# lab6_2020-12-28_17-35-51.net
KiCad netlist of a schematic drawn in EasyEDA
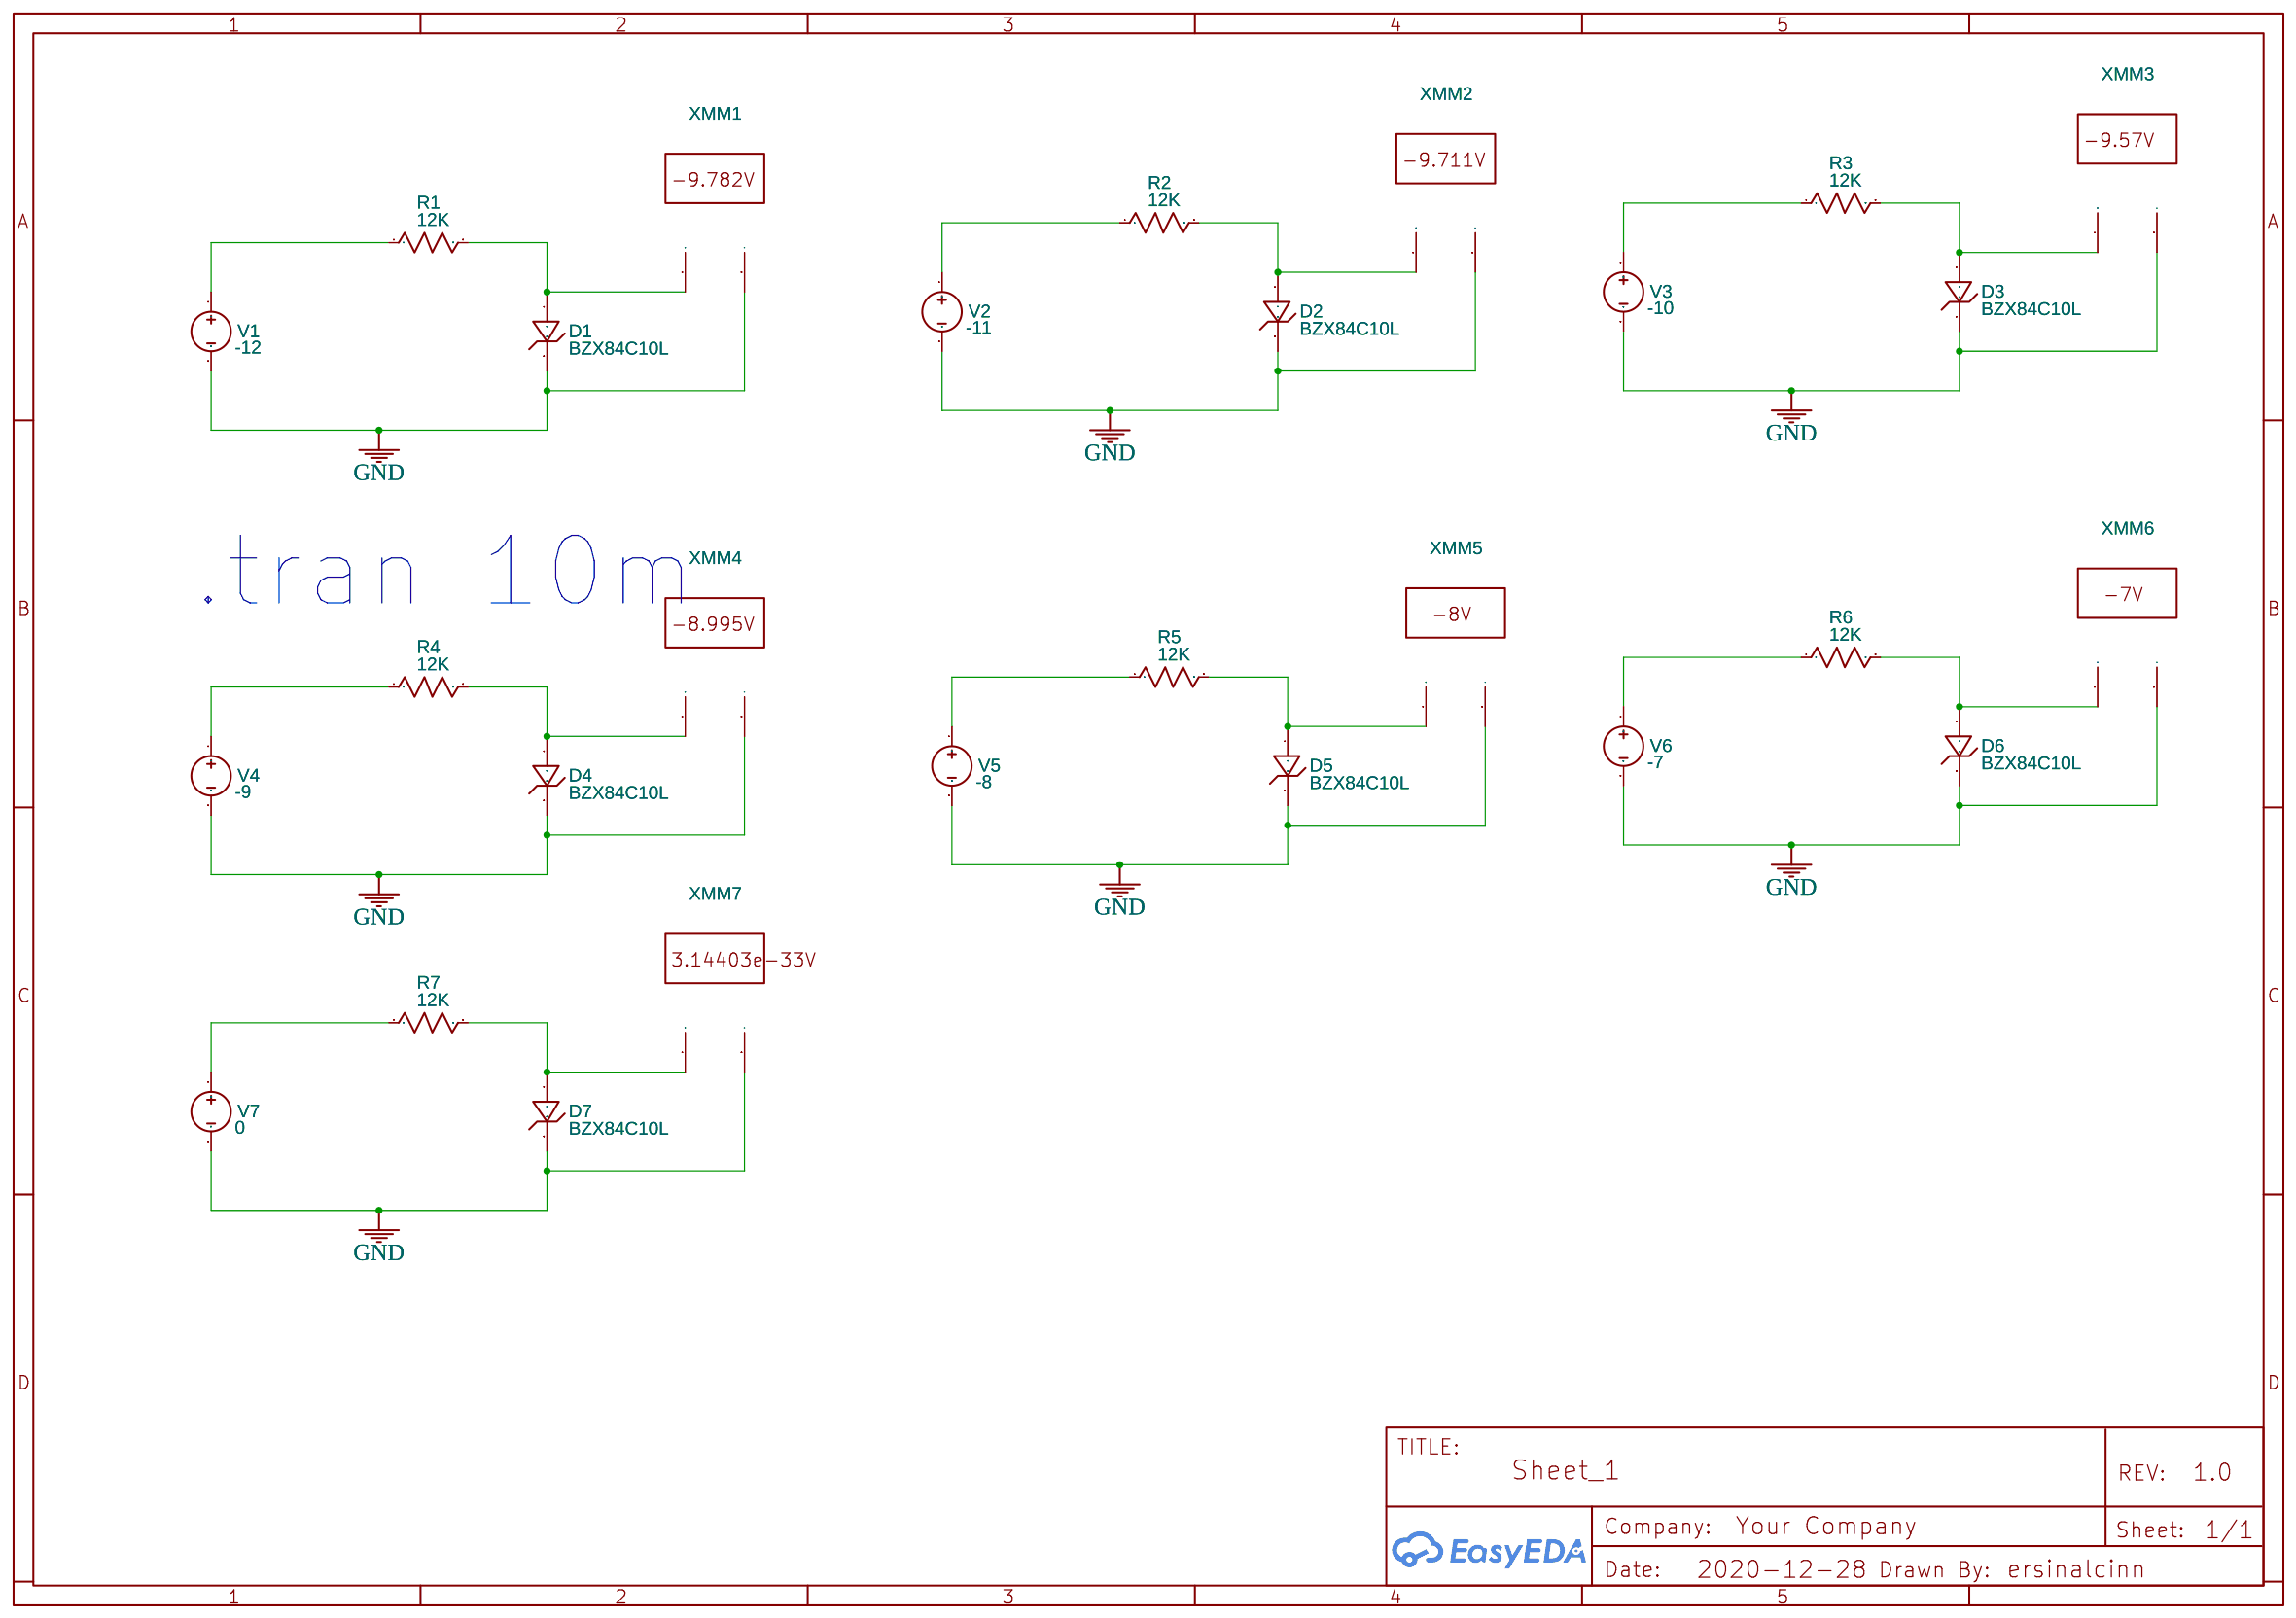
[diagram p0: schematic sheet]

(export (version "E")
  (design (tool "Eeschema 10.0.6"))
  (components
    (comp (ref "D1") (value "BZX84C10L") (libsource (lib "") (part "BZX84C10L")))
    (comp (ref "D2") (value "BZX84C10L") (libsource (lib "") (part "BZX84C10L")))
    (comp (ref "D3") (value "BZX84C10L") (libsource (lib "") (part "BZX84C10L")))
    (comp (ref "D4") (value "BZX84C10L") (libsource (lib "") (part "BZX84C10L")))
    (comp (ref "D5") (value "BZX84C10L") (libsource (lib "") (part "BZX84C10L")))
    (comp (ref "D6") (value "BZX84C10L") (libsource (lib "") (part "BZX84C10L")))
    (comp (ref "D7") (value "BZX84C10L") (libsource (lib "") (part "BZX84C10L")))
    (comp (ref "R1") (value "12K") (libsource (lib "") (part "Resistor_US")))
    (comp (ref "R2") (value "12K") (libsource (lib "") (part "Resistor_US")))
    (comp (ref "R3") (value "12K") (libsource (lib "") (part "Resistor_US")))
    (comp (ref "R4") (value "12K") (libsource (lib "") (part "Resistor_US")))
    (comp (ref "R5") (value "12K") (libsource (lib "") (part "Resistor_US")))
    (comp (ref "R6") (value "12K") (libsource (lib "") (part "Resistor_US")))
    (comp (ref "R7") (value "12K") (libsource (lib "") (part "Resistor_US")))
    (comp (ref "V1") (value "-12") (libsource (lib "") (part "VDC")))
    (comp (ref "V2") (value "-11") (libsource (lib "") (part "VDC")))
    (comp (ref "V3") (value "-10") (libsource (lib "") (part "VDC")))
    (comp (ref "V4") (value "-9") (libsource (lib "") (part "VDC")))
    (comp (ref "V5") (value "-8") (libsource (lib "") (part "VDC")))
    (comp (ref "V6") (value "-7") (libsource (lib "") (part "VDC")))
    (comp (ref "V7") (value "0") (libsource (lib "") (part "VDC")))
    (comp (ref "XMM1") (value "Multimeter") (libsource (lib "") (part "MULTIMETER_3")))
    (comp (ref "XMM2") (value "Multimeter") (libsource (lib "") (part "MULTIMETER_5")))
    (comp (ref "XMM3") (value "Multimeter") (libsource (lib "") (part "MULTIMETER_6")))
    (comp (ref "XMM4") (value "Multimeter") (libsource (lib "") (part "MULTIMETER_1")))
    (comp (ref "XMM5") (value "Multimeter") (libsource (lib "") (part "MULTIMETER_4")))
    (comp (ref "XMM6") (value "Multimeter") (libsource (lib "") (part "MULTIMETER_2")))
    (comp (ref "XMM7") (value "Multimeter") (libsource (lib "") (part "MULTIMETER")))
  )
  (nets
    (net (code "1") (name "GND") (class "Default")
      (node (ref "D1") (pin "2") (pinfunction "K_2") (pintype "unspecified"))
      (node (ref "D2") (pin "2") (pinfunction "K_2") (pintype "unspecified"))
      (node (ref "D3") (pin "2") (pinfunction "K_2") (pintype "unspecified"))
      (node (ref "D4") (pin "2") (pinfunction "K_2") (pintype "unspecified"))
      (node (ref "D5") (pin "2") (pinfunction "K_2") (pintype "unspecified"))
      (node (ref "D6") (pin "2") (pinfunction "K_2") (pintype "unspecified"))
      (node (ref "D7") (pin "2") (pinfunction "K_2") (pintype "unspecified"))
      (node (ref "V1") (pin "2") (pinfunction "2_2") (pintype "unspecified"))
      (node (ref "V2") (pin "2") (pinfunction "2_2") (pintype "unspecified"))
      (node (ref "V3") (pin "2") (pinfunction "2_2") (pintype "unspecified"))
      (node (ref "V4") (pin "2") (pinfunction "2_2") (pintype "unspecified"))
      (node (ref "V5") (pin "2") (pinfunction "2_2") (pintype "unspecified"))
      (node (ref "V6") (pin "2") (pinfunction "2_2") (pintype "unspecified"))
      (node (ref "V7") (pin "2") (pinfunction "2_2") (pintype "unspecified"))
      (node (ref "XMM1") (pin "2") (pinfunction "I_2") (pintype "unspecified"))
      (node (ref "XMM2") (pin "2") (pinfunction "I_2") (pintype "unspecified"))
      (node (ref "XMM3") (pin "2") (pinfunction "I_2") (pintype "unspecified"))
      (node (ref "XMM4") (pin "2") (pinfunction "I_2") (pintype "unspecified"))
      (node (ref "XMM5") (pin "2") (pinfunction "I_2") (pintype "unspecified"))
      (node (ref "XMM6") (pin "2") (pinfunction "I_2") (pintype "unspecified"))
      (node (ref "XMM7") (pin "2") (pinfunction "I_2") (pintype "unspecified"))
    )
    (net (code "2") (name "Net-(D1-A)") (class "Default")
      (node (ref "D1") (pin "1") (pinfunction "A_1") (pintype "unspecified"))
      (node (ref "R1") (pin "2") (pinfunction "2_2") (pintype "unspecified"))
      (node (ref "XMM1") (pin "1") (pinfunction "+_1") (pintype "unspecified"))
    )
    (net (code "3") (name "Net-(D2-A)") (class "Default")
      (node (ref "D2") (pin "1") (pinfunction "A_1") (pintype "unspecified"))
      (node (ref "R2") (pin "2") (pinfunction "2_2") (pintype "unspecified"))
      (node (ref "XMM2") (pin "1") (pinfunction "+_1") (pintype "unspecified"))
    )
    (net (code "4") (name "Net-(D3-A)") (class "Default")
      (node (ref "D3") (pin "1") (pinfunction "A_1") (pintype "unspecified"))
      (node (ref "R3") (pin "2") (pinfunction "2_2") (pintype "unspecified"))
      (node (ref "XMM3") (pin "1") (pinfunction "+_1") (pintype "unspecified"))
    )
    (net (code "5") (name "Net-(D4-A)") (class "Default")
      (node (ref "D4") (pin "1") (pinfunction "A_1") (pintype "unspecified"))
      (node (ref "R4") (pin "2") (pinfunction "2_2") (pintype "unspecified"))
      (node (ref "XMM4") (pin "1") (pinfunction "+_1") (pintype "unspecified"))
    )
    (net (code "6") (name "Net-(D5-A)") (class "Default")
      (node (ref "D5") (pin "1") (pinfunction "A_1") (pintype "unspecified"))
      (node (ref "R5") (pin "2") (pinfunction "2_2") (pintype "unspecified"))
      (node (ref "XMM5") (pin "1") (pinfunction "+_1") (pintype "unspecified"))
    )
    (net (code "7") (name "Net-(D6-A)") (class "Default")
      (node (ref "D6") (pin "1") (pinfunction "A_1") (pintype "unspecified"))
      (node (ref "R6") (pin "2") (pinfunction "2_2") (pintype "unspecified"))
      (node (ref "XMM6") (pin "1") (pinfunction "+_1") (pintype "unspecified"))
    )
    (net (code "8") (name "Net-(D7-A)") (class "Default")
      (node (ref "D7") (pin "1") (pinfunction "A_1") (pintype "unspecified"))
      (node (ref "R7") (pin "2") (pinfunction "2_2") (pintype "unspecified"))
      (node (ref "XMM7") (pin "1") (pinfunction "+_1") (pintype "unspecified"))
    )
    (net (code "9") (name "Net-(R1-Pad1)") (class "Default")
      (node (ref "R1") (pin "1") (pinfunction "1_1") (pintype "unspecified"))
      (node (ref "V1") (pin "1") (pinfunction "1_1") (pintype "unspecified"))
    )
    (net (code "10") (name "Net-(R2-Pad1)") (class "Default")
      (node (ref "R2") (pin "1") (pinfunction "1_1") (pintype "unspecified"))
      (node (ref "V2") (pin "1") (pinfunction "1_1") (pintype "unspecified"))
    )
    (net (code "11") (name "Net-(R3-Pad1)") (class "Default")
      (node (ref "R3") (pin "1") (pinfunction "1_1") (pintype "unspecified"))
      (node (ref "V3") (pin "1") (pinfunction "1_1") (pintype "unspecified"))
    )
    (net (code "12") (name "Net-(R4-Pad1)") (class "Default")
      (node (ref "R4") (pin "1") (pinfunction "1_1") (pintype "unspecified"))
      (node (ref "V4") (pin "1") (pinfunction "1_1") (pintype "unspecified"))
    )
    (net (code "13") (name "Net-(R5-Pad1)") (class "Default")
      (node (ref "R5") (pin "1") (pinfunction "1_1") (pintype "unspecified"))
      (node (ref "V5") (pin "1") (pinfunction "1_1") (pintype "unspecified"))
    )
    (net (code "14") (name "Net-(R6-Pad1)") (class "Default")
      (node (ref "R6") (pin "1") (pinfunction "1_1") (pintype "unspecified"))
      (node (ref "V6") (pin "1") (pinfunction "1_1") (pintype "unspecified"))
    )
    (net (code "15") (name "Net-(R7-Pad1)") (class "Default")
      (node (ref "R7") (pin "1") (pinfunction "1_1") (pintype "unspecified"))
      (node (ref "V7") (pin "1") (pinfunction "1_1") (pintype "unspecified"))
    )
  )
)
